# RP2350.net
KiCad netlist of a schematic drawn in Altium Designer
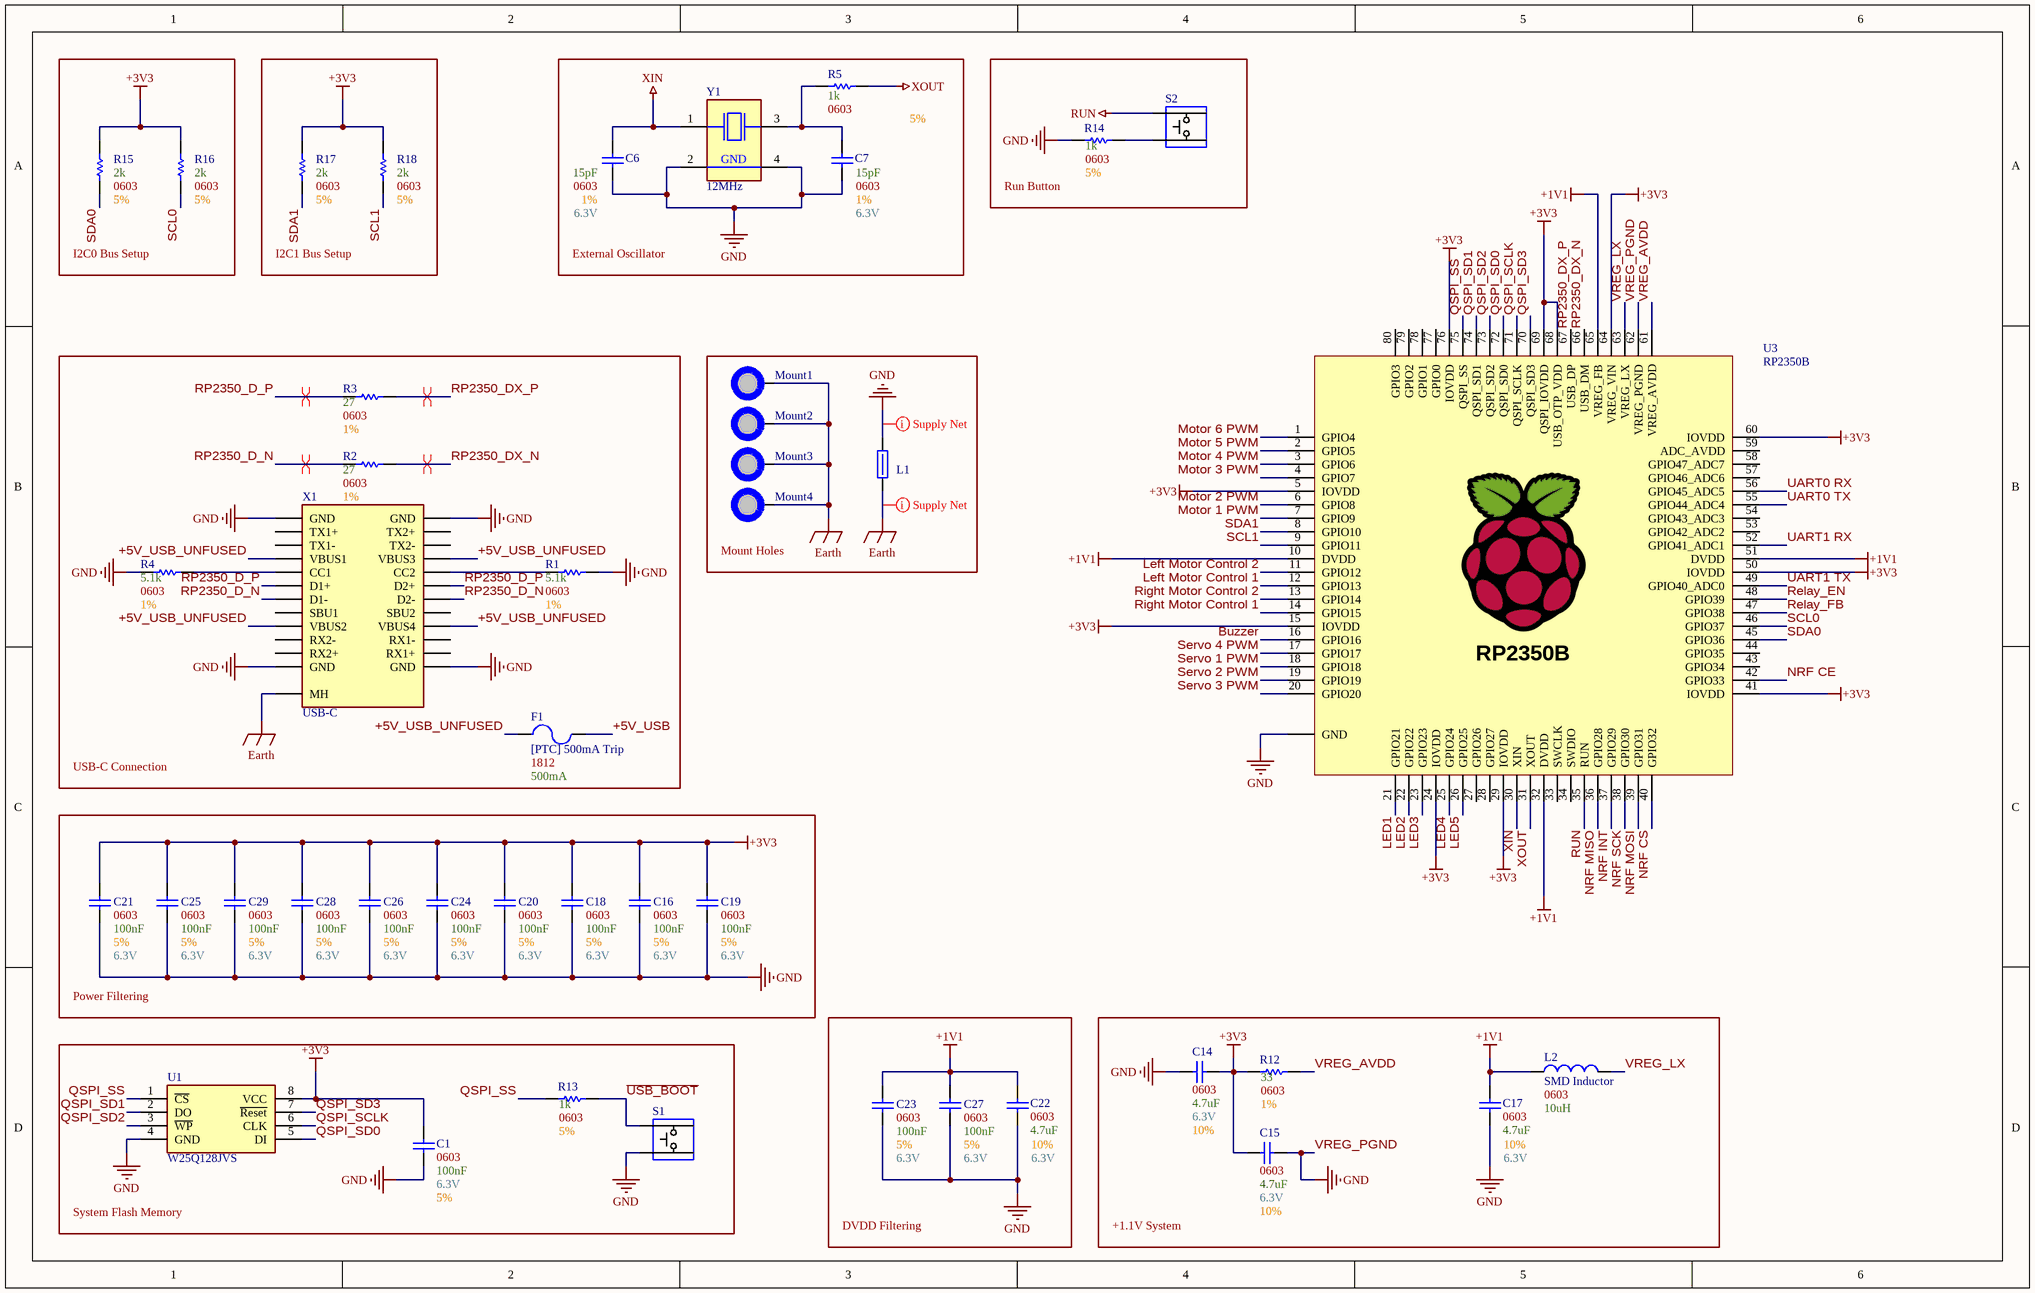
[diagram p0: RP2350.SchDoc]

(export (version "E")
  (design (tool "Eeschema 10.0.6"))
  (components
    (comp (ref "C1")
      (value "[Cap] SMD Nonpolarized")
      (footprint "[Cap] SMD 0603")
      (fields
        (field (name "SIZE PACKAGE") "0603")
        (field (name "CAPACITANCE") "100nF")
        (field (name "VOLTAGE") "6.3V")
        (field (name "TOLERANCE") "5%")
      )
      (libsource (lib "RADM Components") (part "[Cap] SMD Nonpolarized"))
    )
    (comp (ref "C6")
      (value "[Cap] SMD Nonpolarized")
      (footprint "[Cap] SMD 0603")
      (fields
        (field (name "SIZE PACKAGE") "0603")
        (field (name "CAPACITANCE") "15pF")
        (field (name "VOLTAGE") "6.3V")
        (field (name "TOLERANCE") "1%")
      )
      (libsource (lib "RADM Components") (part "[Cap] SMD Nonpolarized"))
    )
    (comp (ref "C7")
      (value "[Cap] SMD Nonpolarized")
      (footprint "[Cap] SMD 0603")
      (fields
        (field (name "SIZE PACKAGE") "0603")
        (field (name "CAPACITANCE") "15pF")
        (field (name "VOLTAGE") "6.3V")
        (field (name "TOLERANCE") "1%")
      )
      (libsource (lib "RADM Components") (part "[Cap] SMD Nonpolarized"))
    )
    (comp (ref "C14")
      (value "[Cap] SMD Nonpolarized")
      (footprint "[Cap] SMD 0603")
      (fields
        (field (name "SIZE PACKAGE") "0603")
        (field (name "CAPACITANCE") "4.7uF")
        (field (name "VOLTAGE") "6.3V")
        (field (name "TOLERANCE") "10%")
      )
      (libsource (lib "RADM Components") (part "[Cap] SMD Nonpolarized"))
    )
    (comp (ref "C15")
      (value "[Cap] SMD Nonpolarized")
      (footprint "[Cap] SMD 0603")
      (fields
        (field (name "SIZE PACKAGE") "0603")
        (field (name "CAPACITANCE") "4.7uF")
        (field (name "VOLTAGE") "6.3V")
        (field (name "TOLERANCE") "10%")
      )
      (libsource (lib "RADM Components") (part "[Cap] SMD Nonpolarized"))
    )
    (comp (ref "C16")
      (value "[Cap] SMD Nonpolarized")
      (footprint "[Cap] SMD 0603")
      (fields
        (field (name "SIZE PACKAGE") "0603")
        (field (name "CAPACITANCE") "100nF")
        (field (name "VOLTAGE") "6.3V")
        (field (name "TOLERANCE") "5%")
      )
      (libsource (lib "RADM Components") (part "[Cap] SMD Nonpolarized"))
    )
    (comp (ref "C17")
      (value "[Cap] SMD Nonpolarized")
      (footprint "[Cap] SMD 0603")
      (fields
        (field (name "SIZE PACKAGE") "0603")
        (field (name "CAPACITANCE") "4.7uF")
        (field (name "VOLTAGE") "6.3V")
        (field (name "TOLERANCE") "10%")
      )
      (libsource (lib "RADM Components") (part "[Cap] SMD Nonpolarized"))
    )
    (comp (ref "C18")
      (value "[Cap] SMD Nonpolarized")
      (footprint "[Cap] SMD 0603")
      (fields
        (field (name "SIZE PACKAGE") "0603")
        (field (name "CAPACITANCE") "100nF")
        (field (name "VOLTAGE") "6.3V")
        (field (name "TOLERANCE") "5%")
      )
      (libsource (lib "RADM Components") (part "[Cap] SMD Nonpolarized"))
    )
    (comp (ref "C19")
      (value "[Cap] SMD Nonpolarized")
      (footprint "[Cap] SMD 0603")
      (fields
        (field (name "SIZE PACKAGE") "0603")
        (field (name "CAPACITANCE") "100nF")
        (field (name "VOLTAGE") "6.3V")
        (field (name "TOLERANCE") "5%")
      )
      (libsource (lib "RADM Components") (part "[Cap] SMD Nonpolarized"))
    )
    (comp (ref "C20")
      (value "[Cap] SMD Nonpolarized")
      (footprint "[Cap] SMD 0603")
      (fields
        (field (name "SIZE PACKAGE") "0603")
        (field (name "CAPACITANCE") "100nF")
        (field (name "VOLTAGE") "6.3V")
        (field (name "TOLERANCE") "5%")
      )
      (libsource (lib "RADM Components") (part "[Cap] SMD Nonpolarized"))
    )
    (comp (ref "C21")
      (value "[Cap] SMD Nonpolarized")
      (footprint "[Cap] SMD 0603")
      (fields
        (field (name "SIZE PACKAGE") "0603")
        (field (name "CAPACITANCE") "100nF")
        (field (name "VOLTAGE") "6.3V")
        (field (name "TOLERANCE") "5%")
      )
      (libsource (lib "RADM Components") (part "[Cap] SMD Nonpolarized"))
    )
    (comp (ref "C22")
      (value "[Cap] SMD Nonpolarized")
      (footprint "[Cap] SMD 0603")
      (fields
        (field (name "SIZE PACKAGE") "0603")
        (field (name "CAPACITANCE") "4.7uF")
        (field (name "VOLTAGE") "6.3V")
        (field (name "TOLERANCE") "10%")
      )
      (libsource (lib "RADM Components") (part "[Cap] SMD Nonpolarized"))
    )
    (comp (ref "C23")
      (value "[Cap] SMD Nonpolarized")
      (footprint "[Cap] SMD 0603")
      (fields
        (field (name "SIZE PACKAGE") "0603")
        (field (name "CAPACITANCE") "100nF")
        (field (name "VOLTAGE") "6.3V")
        (field (name "TOLERANCE") "5%")
      )
      (libsource (lib "RADM Components") (part "[Cap] SMD Nonpolarized"))
    )
    (comp (ref "C24")
      (value "[Cap] SMD Nonpolarized")
      (footprint "[Cap] SMD 0603")
      (fields
        (field (name "SIZE PACKAGE") "0603")
        (field (name "CAPACITANCE") "100nF")
        (field (name "VOLTAGE") "6.3V")
        (field (name "TOLERANCE") "5%")
      )
      (libsource (lib "RADM Components") (part "[Cap] SMD Nonpolarized"))
    )
    (comp (ref "C25")
      (value "[Cap] SMD Nonpolarized")
      (footprint "[Cap] SMD 0603")
      (fields
        (field (name "SIZE PACKAGE") "0603")
        (field (name "CAPACITANCE") "100nF")
        (field (name "VOLTAGE") "6.3V")
        (field (name "TOLERANCE") "5%")
      )
      (libsource (lib "RADM Components") (part "[Cap] SMD Nonpolarized"))
    )
    (comp (ref "C26")
      (value "[Cap] SMD Nonpolarized")
      (footprint "[Cap] SMD 0603")
      (fields
        (field (name "SIZE PACKAGE") "0603")
        (field (name "CAPACITANCE") "100nF")
        (field (name "VOLTAGE") "6.3V")
        (field (name "TOLERANCE") "5%")
      )
      (libsource (lib "RADM Components") (part "[Cap] SMD Nonpolarized"))
    )
    (comp (ref "C27")
      (value "[Cap] SMD Nonpolarized")
      (footprint "[Cap] SMD 0603")
      (fields
        (field (name "SIZE PACKAGE") "0603")
        (field (name "CAPACITANCE") "100nF")
        (field (name "VOLTAGE") "6.3V")
        (field (name "TOLERANCE") "5%")
      )
      (libsource (lib "RADM Components") (part "[Cap] SMD Nonpolarized"))
    )
    (comp (ref "C28")
      (value "[Cap] SMD Nonpolarized")
      (footprint "[Cap] SMD 0603")
      (fields
        (field (name "SIZE PACKAGE") "0603")
        (field (name "CAPACITANCE") "100nF")
        (field (name "VOLTAGE") "6.3V")
        (field (name "TOLERANCE") "5%")
      )
      (libsource (lib "RADM Components") (part "[Cap] SMD Nonpolarized"))
    )
    (comp (ref "C29")
      (value "[Cap] SMD Nonpolarized")
      (footprint "[Cap] SMD 0603")
      (fields
        (field (name "SIZE PACKAGE") "0603")
        (field (name "CAPACITANCE") "100nF")
        (field (name "VOLTAGE") "6.3V")
        (field (name "TOLERANCE") "5%")
      )
      (libsource (lib "RADM Components") (part "[Cap] SMD Nonpolarized"))
    )
    (comp (ref "F1")
      (value "[PTC] 500mA Trip")
      (footprint "[PTC] 500mA Trip")
      (description "MF-MSMF050-2")
      (fields (field (name "SIZE PACKAGE") "1812") (field (name "TRIP CURRENT") "500mA"))
      (libsource (lib "RADM Components") (part "[PTC] 500mA Trip"))
    )
    (comp (ref "L1")
      (value "652-MH2029-300Y")
      (footprint "[Ferrite] SMD Bead 0805 (1)")
      (libsource (lib "RADM Components") (part "[Ferrite] SMD Ferrite Bead (1)"))
    )
    (comp (ref "L2")
      (value "SMD Inductor")
      (footprint "[Inductor] SMD 0603")
      (fields (field (name "SIZE PACKAGE") "0603") (field (name "INDUCTANCE") "10uH"))
      (libsource (lib "RADM Components") (part "[Inductor] SMD Inductor"))
    )
    (comp (ref "Mount1")
      (value "M3 Mount Hole")
      (footprint "[Mount] M3 Mount Hole")
      (description "Place at least 4.5mm from board edge. Plated.")
      (libsource (lib "RADM Connectors") (part "[Mount] M3 Mount Hole"))
    )
    (comp (ref "Mount2")
      (value "M3 Mount Hole")
      (footprint "[Mount] M3 Mount Hole")
      (description "Place at least 4.5mm from board edge. Plated.")
      (libsource (lib "RADM Connectors") (part "[Mount] M3 Mount Hole"))
    )
    (comp (ref "Mount3")
      (value "M3 Mount Hole")
      (footprint "[Mount] M3 Mount Hole")
      (description "Place at least 4.5mm from board edge. Plated.")
      (libsource (lib "RADM Connectors") (part "[Mount] M3 Mount Hole"))
    )
    (comp (ref "Mount4")
      (value "M3 Mount Hole")
      (footprint "[Mount] M3 Mount Hole")
      (description "Place at least 4.5mm from board edge. Plated.")
      (libsource (lib "RADM Connectors") (part "[Mount] M3 Mount Hole"))
    )
    (comp (ref "R1")
      (value "[Res] SMD Resistor")
      (footprint "[Res] SMD 0603")
      (description "Generic")
      (fields
        (field (name "TOLERANCE") "1%")
        (field (name "RESISTANCE") "5.1k")
        (field (name "SIZE PACKAGE") "0603")
      )
      (libsource (lib "RADM Components") (part "[Res] SMD Resistor"))
    )
    (comp (ref "R2")
      (value "[Res] SMD Resistor")
      (footprint "[Res] SMD 0603")
      (description "Generic")
      (fields
        (field (name "TOLERANCE") "1%")
        (field (name "RESISTANCE") "27")
        (field (name "SIZE PACKAGE") "0603")
      )
      (libsource (lib "RADM Components") (part "[Res] SMD Resistor"))
    )
    (comp (ref "R3")
      (value "[Res] SMD Resistor")
      (footprint "[Res] SMD 0603")
      (description "Generic")
      (fields
        (field (name "TOLERANCE") "1%")
        (field (name "RESISTANCE") "27")
        (field (name "SIZE PACKAGE") "0603")
      )
      (libsource (lib "RADM Components") (part "[Res] SMD Resistor"))
    )
    (comp (ref "R4")
      (value "[Res] SMD Resistor")
      (footprint "[Res] SMD 0603")
      (description "Generic")
      (fields
        (field (name "TOLERANCE") "1%")
        (field (name "RESISTANCE") "5.1k")
        (field (name "SIZE PACKAGE") "0603")
      )
      (libsource (lib "RADM Components") (part "[Res] SMD Resistor"))
    )
    (comp (ref "R5")
      (value "[Res] SMD Resistor")
      (footprint "[Res] SMD 0603")
      (description "Generic")
      (fields
        (field (name "RESISTANCE") "1k")
        (field (name "SIZE PACKAGE") "0603")
        (field (name "TOLERANCE") "5%")
      )
      (libsource (lib "RADM Components") (part "[Res] SMD Resistor"))
    )
    (comp (ref "R12")
      (value "[Res] SMD Resistor")
      (footprint "[Res] SMD 0603")
      (description "Generic")
      (fields
        (field (name "RESISTANCE") "33")
        (field (name "SIZE PACKAGE") "0603")
        (field (name "TOLERANCE") "1%")
      )
      (libsource (lib "RADM Components") (part "[Res] SMD Resistor"))
    )
    (comp (ref "R13")
      (value "[Res] SMD Resistor")
      (footprint "[Res] SMD 0603")
      (description "Generic")
      (fields
        (field (name "RESISTANCE") "1k")
        (field (name "SIZE PACKAGE") "0603")
        (field (name "TOLERANCE") "5%")
      )
      (libsource (lib "RADM Components") (part "[Res] SMD Resistor"))
    )
    (comp (ref "R14")
      (value "[Res] SMD Resistor")
      (footprint "[Res] SMD 0603")
      (description "Generic")
      (fields
        (field (name "RESISTANCE") "1k")
        (field (name "SIZE PACKAGE") "0603")
        (field (name "TOLERANCE") "5%")
      )
      (libsource (lib "RADM Components") (part "[Res] SMD Resistor"))
    )
    (comp (ref "R15")
      (value "[Res] SMD Resistor")
      (footprint "[Res] SMD 0603")
      (description "Generic")
      (fields
        (field (name "RESISTANCE") "2k")
        (field (name "SIZE PACKAGE") "0603")
        (field (name "TOLERANCE") "5%")
      )
      (libsource (lib "RADM Components") (part "[Res] SMD Resistor"))
    )
    (comp (ref "R16")
      (value "[Res] SMD Resistor")
      (footprint "[Res] SMD 0603")
      (description "Generic")
      (fields
        (field (name "RESISTANCE") "2k")
        (field (name "SIZE PACKAGE") "0603")
        (field (name "TOLERANCE") "5%")
      )
      (libsource (lib "RADM Components") (part "[Res] SMD Resistor"))
    )
    (comp (ref "R17")
      (value "[Res] SMD Resistor")
      (footprint "[Res] SMD 0603")
      (description "Generic")
      (fields
        (field (name "RESISTANCE") "2k")
        (field (name "SIZE PACKAGE") "0603")
        (field (name "TOLERANCE") "5%")
      )
      (libsource (lib "RADM Components") (part "[Res] SMD Resistor"))
    )
    (comp (ref "R18")
      (value "[Res] SMD Resistor")
      (footprint "[Res] SMD 0603")
      (description "Generic")
      (fields
        (field (name "RESISTANCE") "2k")
        (field (name "SIZE PACKAGE") "0603")
        (field (name "TOLERANCE") "5%")
      )
      (libsource (lib "RADM Components") (part "[Res] SMD Resistor"))
    )
    (comp (ref "S1")
      (value "Standard pushbutton")
      (footprint "[Switch] Pushbutton")
      (libsource (lib "RADM Components") (part "[Switch] Pushbutton"))
    )
    (comp (ref "S2")
      (value "Standard pushbutton")
      (footprint "[Switch] Pushbutton")
      (libsource (lib "RADM Components") (part "[Switch] Pushbutton"))
    )
    (comp (ref "U1")
      (value "W25Q128JVS")
      (footprint "[Mem] 16Mb Flash Memory")
      (description "W25Q128JVSIQ TR")
      (libsource (lib "RADM Components") (part "[Mem] 16Mb Flash Memory"))
    )
    (comp (ref "U3")
      (value "RP2350B")
      (footprint "[MCU] RP2350B")
      (description "QFN-80 Package")
      (libsource (lib "RADM Components") (part "[MCU] RP2350B"))
    )
    (comp (ref "X1")
      (value "USB-C")
      (footprint "[Port] USB-C")
      (libsource (lib "RADM Connectors") (part "[Port] USB Type-C"))
    )
    (comp (ref "Y1")
      (value "12MHz")
      (footprint "[XTAL] SMD 12MHz")
      (description "815-ABM8-272-T3")
      (libsource (lib "RADM Components") (part "[XTAL] SMD 12MHz"))
    )
  )
  (nets
    (net (code "1") (name "+1V1") (class "Default")
      (node (ref "C17") (pin "2") (pinfunction "2_2") (pintype "passive"))
      (node (ref "C22") (pin "2") (pinfunction "2_2") (pintype "passive"))
      (node (ref "C23") (pin "2") (pinfunction "2_2") (pintype "passive"))
      (node (ref "C27") (pin "2") (pinfunction "2_2") (pintype "passive"))
      (node (ref "L2") (pin "1") (pinfunction "1_1") (pintype "passive"))
      (node (ref "U3") (pin "10") (pinfunction "DVDD_10") (pintype "passive"))
      (node (ref "U3") (pin "32") (pinfunction "DVDD_32") (pintype "passive"))
      (node (ref "U3") (pin "51") (pinfunction "DVDD_51") (pintype "passive"))
      (node (ref "U3") (pin "65") (pinfunction "VREG_FB_65") (pintype "passive"))
    )
    (net (code "2") (name "+3V3") (class "Default")
      (node (ref "C1") (pin "1") (pinfunction "1_1") (pintype "passive"))
      (node (ref "C14") (pin "1") (pinfunction "1_1") (pintype "passive"))
      (node (ref "C15") (pin "2") (pinfunction "2_2") (pintype "passive"))
      (node (ref "C16") (pin "2") (pinfunction "2_2") (pintype "passive"))
      (node (ref "C18") (pin "2") (pinfunction "2_2") (pintype "passive"))
      (node (ref "C19") (pin "2") (pinfunction "2_2") (pintype "passive"))
      (node (ref "C20") (pin "2") (pinfunction "2_2") (pintype "passive"))
      (node (ref "C21") (pin "2") (pinfunction "2_2") (pintype "passive"))
      (node (ref "C24") (pin "2") (pinfunction "2_2") (pintype "passive"))
      (node (ref "C25") (pin "2") (pinfunction "2_2") (pintype "passive"))
      (node (ref "C26") (pin "2") (pinfunction "2_2") (pintype "passive"))
      (node (ref "C28") (pin "2") (pinfunction "2_2") (pintype "passive"))
      (node (ref "C29") (pin "2") (pinfunction "2_2") (pintype "passive"))
      (node (ref "R12") (pin "2") (pinfunction "2_2") (pintype "passive"))
      (node (ref "R15") (pin "2") (pinfunction "2_2") (pintype "passive"))
      (node (ref "R16") (pin "2") (pinfunction "2_2") (pintype "passive"))
      (node (ref "R17") (pin "2") (pinfunction "2_2") (pintype "passive"))
      (node (ref "R18") (pin "2") (pinfunction "2_2") (pintype "passive"))
      (node (ref "U1") (pin "8") (pinfunction "VCC_8") (pintype "passive"))
      (node (ref "U3") (pin "15") (pinfunction "IOVDD_15") (pintype "passive"))
      (node (ref "U3") (pin "24") (pinfunction "IOVDD_24") (pintype "passive"))
      (node (ref "U3") (pin "29") (pinfunction "IOVDD_29") (pintype "passive"))
      (node (ref "U3") (pin "41") (pinfunction "IOVDD_41") (pintype "passive"))
      (node (ref "U3") (pin "5") (pinfunction "IOVDD_5") (pintype "passive"))
      (node (ref "U3") (pin "50") (pinfunction "IOVDD_50") (pintype "passive"))
      (node (ref "U3") (pin "60") (pinfunction "IOVDD_60") (pintype "passive"))
      (node (ref "U3") (pin "64") (pinfunction "VREG_VIN_64") (pintype "passive"))
      (node (ref "U3") (pin "68") (pinfunction "USB_OTP_VDD_68") (pintype "passive"))
      (node (ref "U3") (pin "69") (pinfunction "QSPI_IOVDD_69") (pintype "passive"))
      (node (ref "U3") (pin "76") (pinfunction "IOVDD_76") (pintype "passive"))
    )
    (net (code "3") (name "/+5V_USB") (class "Default")
      (node (ref "F1") (pin "2") (pinfunction "2_2") (pintype "passive"))
    )
    (net (code "4") (name "/+5V_USB_UNFUSED") (class "Default")
      (node (ref "F1") (pin "1") (pinfunction "1_1") (pintype "passive"))
      (node (ref "X1") (pin "A4") (pinfunction "VBUS1_A4") (pintype "passive"))
      (node (ref "X1") (pin "A9") (pinfunction "VBUS2_A9") (pintype "passive"))
      (node (ref "X1") (pin "B4") (pinfunction "VBUS3_B4") (pintype "passive"))
      (node (ref "X1") (pin "B9") (pinfunction "VBUS4_B9") (pintype "passive"))
    )
    (net (code "5") (name "/Buzzer") (class "Default")
      (node (ref "U3") (pin "16") (pinfunction "GPIO16_16") (pintype "passive"))
    )
    (net (code "6") (name "/LED1") (class "Default")
      (node (ref "U3") (pin "21") (pinfunction "GPIO21_21") (pintype "passive"))
    )
    (net (code "7") (name "/LED2") (class "Default")
      (node (ref "U3") (pin "22") (pinfunction "GPIO22_22") (pintype "passive"))
    )
    (net (code "8") (name "/LED3") (class "Default")
      (node (ref "U3") (pin "23") (pinfunction "GPIO23_23") (pintype "passive"))
    )
    (net (code "9") (name "/LED4") (class "Default")
      (node (ref "U3") (pin "25") (pinfunction "GPIO24_25") (pintype "passive"))
    )
    (net (code "10") (name "/LED5") (class "Default")
      (node (ref "U3") (pin "26") (pinfunction "GPIO25_26") (pintype "passive"))
    )
    (net (code "11") (name "/Left Motor Control 1") (class "Default")
      (node (ref "U3") (pin "12") (pinfunction "GPIO13_12") (pintype "passive"))
    )
    (net (code "12") (name "/Left Motor Control 2") (class "Default")
      (node (ref "U3") (pin "11") (pinfunction "GPIO12_11") (pintype "passive"))
    )
    (net (code "13") (name "/Motor 1 PWM") (class "Default")
      (node (ref "U3") (pin "7") (pinfunction "GPIO9_7") (pintype "passive"))
    )
    (net (code "14") (name "/Motor 2 PWM") (class "Default")
      (node (ref "U3") (pin "6") (pinfunction "GPIO8_6") (pintype "passive"))
    )
    (net (code "15") (name "/Motor 3 PWM") (class "Default")
      (node (ref "U3") (pin "4") (pinfunction "GPIO7_4") (pintype "passive"))
    )
    (net (code "16") (name "/Motor 4 PWM") (class "Default")
      (node (ref "U3") (pin "3") (pinfunction "GPIO6_3") (pintype "passive"))
    )
    (net (code "17") (name "/Motor 5 PWM") (class "Default")
      (node (ref "U3") (pin "2") (pinfunction "GPIO5_2") (pintype "passive"))
    )
    (net (code "18") (name "/Motor 6 PWM") (class "Default")
      (node (ref "U3") (pin "1") (pinfunction "GPIO4_1") (pintype "passive"))
    )
    (net (code "19") (name "/NRF CE") (class "Default")
      (node (ref "U3") (pin "42") (pinfunction "GPIO33_42") (pintype "passive"))
    )
    (net (code "20") (name "/NRF CS") (class "Default")
      (node (ref "U3") (pin "40") (pinfunction "GPIO32_40") (pintype "passive"))
    )
    (net (code "21") (name "/NRF INT") (class "Default")
      (node (ref "U3") (pin "37") (pinfunction "GPIO29_37") (pintype "passive"))
    )
    (net (code "22") (name "/NRF MISO") (class "Default")
      (node (ref "U3") (pin "36") (pinfunction "GPIO28_36") (pintype "passive"))
    )
    (net (code "23") (name "/NRF MOSI") (class "Default")
      (node (ref "U3") (pin "39") (pinfunction "GPIO31_39") (pintype "passive"))
    )
    (net (code "24") (name "/NRF SCK") (class "Default")
      (node (ref "U3") (pin "38") (pinfunction "GPIO30_38") (pintype "passive"))
    )
    (net (code "25") (name "/QSPI_SCLK") (class "Default")
      (node (ref "U1") (pin "6") (pinfunction "CLK_6") (pintype "passive"))
      (node (ref "U3") (pin "71") (pinfunction "QSPI_SCLK_71") (pintype "passive"))
    )
    (net (code "26") (name "/QSPI_SD0") (class "Default")
      (node (ref "U1") (pin "5") (pinfunction "DI_5") (pintype "passive"))
      (node (ref "U3") (pin "72") (pinfunction "QSPI_SD0_72") (pintype "passive"))
    )
    (net (code "27") (name "/QSPI_SD1") (class "Default")
      (node (ref "U1") (pin "2") (pinfunction "DO_2") (pintype "passive"))
      (node (ref "U3") (pin "74") (pinfunction "QSPI_SD1_74") (pintype "passive"))
    )
    (net (code "28") (name "/QSPI_SD2") (class "Default")
      (node (ref "U1") (pin "3") (pinfunction "~{WP}_3") (pintype "passive"))
      (node (ref "U3") (pin "73") (pinfunction "QSPI_SD2_73") (pintype "passive"))
    )
    (net (code "29") (name "/QSPI_SD3") (class "Default")
      (node (ref "U1") (pin "7") (pinfunction "~{Reset}_7") (pintype "passive"))
      (node (ref "U3") (pin "70") (pinfunction "QSPI_SD3_70") (pintype "passive"))
    )
    (net (code "30") (name "/QSPI_SS") (class "Default")
      (node (ref "R13") (pin "2") (pinfunction "2_2") (pintype "passive"))
      (node (ref "U1") (pin "1") (pinfunction "~{CS}_1") (pintype "passive"))
      (node (ref "U3") (pin "75") (pinfunction "QSPI_SS_75") (pintype "passive"))
    )
    (net (code "31") (name "/RP2350_DX_N") (class "Default")
      (node (ref "R2") (pin "2") (pinfunction "2_2") (pintype "passive"))
      (node (ref "U3") (pin "66") (pinfunction "USB_DM_66") (pintype "passive"))
    )
    (net (code "32") (name "/RP2350_DX_P") (class "Default")
      (node (ref "R3") (pin "2") (pinfunction "2_2") (pintype "passive"))
      (node (ref "U3") (pin "67") (pinfunction "USB_DP_67") (pintype "passive"))
    )
    (net (code "33") (name "/RP2350_D_N") (class "Default")
      (node (ref "R2") (pin "1") (pinfunction "1_1") (pintype "passive"))
      (node (ref "X1") (pin "A7") (pinfunction "D1-_A7") (pintype "passive"))
      (node (ref "X1") (pin "B7") (pinfunction "D2-_B7") (pintype "passive"))
    )
    (net (code "34") (name "/RP2350_D_P") (class "Default")
      (node (ref "R3") (pin "1") (pinfunction "1_1") (pintype "passive"))
      (node (ref "X1") (pin "A6") (pinfunction "D1+_A6") (pintype "passive"))
      (node (ref "X1") (pin "B6") (pinfunction "D2+_B6") (pintype "passive"))
    )
    (net (code "35") (name "/Relay_EN") (class "Default")
      (node (ref "U3") (pin "48") (pinfunction "GPIO39_48") (pintype "passive"))
    )
    (net (code "36") (name "/Relay_FB") (class "Default")
      (node (ref "U3") (pin "47") (pinfunction "GPIO38_47") (pintype "passive"))
    )
    (net (code "37") (name "/Right Motor Control 1") (class "Default")
      (node (ref "U3") (pin "14") (pinfunction "GPIO15_14") (pintype "passive"))
    )
    (net (code "38") (name "/Right Motor Control 2") (class "Default")
      (node (ref "U3") (pin "13") (pinfunction "GPIO14_13") (pintype "passive"))
    )
    (net (code "39") (name "/SCL0") (class "Default")
      (node (ref "R16") (pin "1") (pinfunction "1_1") (pintype "passive"))
      (node (ref "U3") (pin "46") (pinfunction "GPIO37_46") (pintype "passive"))
    )
    (net (code "40") (name "/SCL1") (class "Default")
      (node (ref "R18") (pin "1") (pinfunction "1_1") (pintype "passive"))
      (node (ref "U3") (pin "9") (pinfunction "GPIO11_9") (pintype "passive"))
    )
    (net (code "41") (name "/SDA0") (class "Default")
      (node (ref "R15") (pin "1") (pinfunction "1_1") (pintype "passive"))
      (node (ref "U3") (pin "45") (pinfunction "GPIO36_45") (pintype "passive"))
    )
    (net (code "42") (name "/SDA1") (class "Default")
      (node (ref "R17") (pin "1") (pinfunction "1_1") (pintype "passive"))
      (node (ref "U3") (pin "8") (pinfunction "GPIO10_8") (pintype "passive"))
    )
    (net (code "43") (name "/Servo 1 PWM") (class "Default")
      (node (ref "U3") (pin "18") (pinfunction "GPIO18_18") (pintype "passive"))
    )
    (net (code "44") (name "/Servo 2 PWM") (class "Default")
      (node (ref "U3") (pin "19") (pinfunction "GPIO19_19") (pintype "passive"))
    )
    (net (code "45") (name "/Servo 3 PWM") (class "Default")
      (node (ref "U3") (pin "20") (pinfunction "GPIO20_20") (pintype "passive"))
    )
    (net (code "46") (name "/Servo 4 PWM") (class "Default")
      (node (ref "U3") (pin "17") (pinfunction "GPIO17_17") (pintype "passive"))
    )
    (net (code "47") (name "/UART0 RX") (class "Default")
      (node (ref "U3") (pin "56") (pinfunction "GPIO45_ADC5_56") (pintype "passive"))
    )
    (net (code "48") (name "/UART0 TX") (class "Default")
      (node (ref "U3") (pin "55") (pinfunction "GPIO44_ADC4_55") (pintype "passive"))
    )
    (net (code "49") (name "/UART1 RX") (class "Default")
      (node (ref "U3") (pin "52") (pinfunction "GPIO41_ADC1_52") (pintype "passive"))
    )
    (net (code "50") (name "/UART1 TX") (class "Default")
      (node (ref "U3") (pin "49") (pinfunction "GPIO40_ADC0_49") (pintype "passive"))
    )
    (net (code "51") (name "/VREG_AVDD") (class "Default")
      (node (ref "R12") (pin "1") (pinfunction "1_1") (pintype "passive"))
      (node (ref "U3") (pin "61") (pinfunction "VREG_AVDD_61") (pintype "passive"))
    )
    (net (code "52") (name "/VREG_LX") (class "Default")
      (node (ref "L2") (pin "2") (pinfunction "2_2") (pintype "passive"))
      (node (ref "U3") (pin "63") (pinfunction "VREG_LX_63") (pintype "passive"))
    )
    (net (code "53") (name "/~{USB_BOOT}") (class "Default")
      (node (ref "R13") (pin "1") (pinfunction "1_1") (pintype "passive"))
      (node (ref "S1") (pin "1") (pintype "power_in"))
    )
    (net (code "54") (name "Earth") (class "Default")
      (node (ref "L1") (pin "1") (pinfunction "1_1") (pintype "passive"))
      (node (ref "Mount1") (pin "1") (pintype "power_in"))
      (node (ref "Mount2") (pin "1") (pintype "power_in"))
      (node (ref "Mount3") (pin "1") (pintype "power_in"))
      (node (ref "Mount4") (pin "1") (pintype "power_in"))
      (node (ref "X1") (pin "MH") (pinfunction "MH_MH") (pintype "passive"))
    )
    (net (code "55") (name "GND") (class "Default")
      (node (ref "C1") (pin "2") (pinfunction "2_2") (pintype "passive"))
      (node (ref "C14") (pin "2") (pinfunction "2_2") (pintype "passive"))
      (node (ref "C15") (pin "1") (pinfunction "1_1") (pintype "passive"))
      (node (ref "C16") (pin "1") (pinfunction "1_1") (pintype "passive"))
      (node (ref "C17") (pin "1") (pinfunction "1_1") (pintype "passive"))
      (node (ref "C18") (pin "1") (pinfunction "1_1") (pintype "passive"))
      (node (ref "C19") (pin "1") (pinfunction "1_1") (pintype "passive"))
      (node (ref "C20") (pin "1") (pinfunction "1_1") (pintype "passive"))
      (node (ref "C21") (pin "1") (pinfunction "1_1") (pintype "passive"))
      (node (ref "C22") (pin "1") (pinfunction "1_1") (pintype "passive"))
      (node (ref "C23") (pin "1") (pinfunction "1_1") (pintype "passive"))
      (node (ref "C24") (pin "1") (pinfunction "1_1") (pintype "passive"))
      (node (ref "C25") (pin "1") (pinfunction "1_1") (pintype "passive"))
      (node (ref "C26") (pin "1") (pinfunction "1_1") (pintype "passive"))
      (node (ref "C27") (pin "1") (pinfunction "1_1") (pintype "passive"))
      (node (ref "C28") (pin "1") (pinfunction "1_1") (pintype "passive"))
      (node (ref "C29") (pin "1") (pinfunction "1_1") (pintype "passive"))
      (node (ref "C6") (pin "1") (pinfunction "1_1") (pintype "passive"))
      (node (ref "C7") (pin "1") (pinfunction "1_1") (pintype "passive"))
      (node (ref "L1") (pin "2") (pinfunction "2_2") (pintype "passive"))
      (node (ref "R1") (pin "2") (pinfunction "2_2") (pintype "passive"))
      (node (ref "R14") (pin "2") (pinfunction "2_2") (pintype "passive"))
      (node (ref "R4") (pin "1") (pinfunction "1_1") (pintype "passive"))
      (node (ref "S1") (pin "2") (pintype "power_in"))
      (node (ref "U1") (pin "4") (pinfunction "GND_4") (pintype "passive"))
      (node (ref "U3") (pin "62") (pinfunction "VREG_PGND_62") (pintype "passive"))
      (node (ref "U3") (pin "Pad") (pinfunction "GND_Pad") (pintype "passive"))
      (node (ref "X1") (pin "A1") (pinfunction "GND_A1") (pintype "passive"))
      (node (ref "X1") (pin "A12") (pinfunction "GND_A12") (pintype "passive"))
      (node (ref "X1") (pin "B1") (pinfunction "GND_B1") (pintype "passive"))
      (node (ref "X1") (pin "B12") (pinfunction "GND_B12") (pintype "passive"))
      (node (ref "Y1") (pin "2") (pinfunction "GND_2") (pintype "power_in"))
      (node (ref "Y1") (pin "4") (pinfunction "GND_4") (pintype "power_in"))
    )
    (net (code "56") (name "Net-(R14-Pad1)") (class "Default")
      (node (ref "R14") (pin "1") (pinfunction "1_1") (pintype "passive"))
      (node (ref "S2") (pin "2") (pintype "power_in"))
    )
    (net (code "57") (name "Net-(X1-CC1)") (class "Default")
      (node (ref "R4") (pin "2") (pinfunction "2_2") (pintype "passive"))
      (node (ref "X1") (pin "A5") (pinfunction "CC1_A5") (pintype "passive"))
    )
    (net (code "58") (name "Net-(X1-CC2)") (class "Default")
      (node (ref "R1") (pin "1") (pinfunction "1_1") (pintype "passive"))
      (node (ref "X1") (pin "B5") (pinfunction "CC2_B5") (pintype "passive"))
    )
    (net (code "59") (name "Net-(Y1-XTAL2)") (class "Default")
      (node (ref "C7") (pin "2") (pinfunction "2_2") (pintype "passive"))
      (node (ref "R5") (pin "2") (pinfunction "2_2") (pintype "passive"))
      (node (ref "Y1") (pin "3") (pinfunction "XTAL2_3") (pintype "power_in"))
    )
    (net (code "60") (name "RUN") (class "Default")
      (node (ref "S2") (pin "1") (pintype "power_in"))
      (node (ref "U3") (pin "35") (pinfunction "RUN_35") (pintype "passive"))
    )
    (net (code "61") (name "XIN") (class "Default")
      (node (ref "C6") (pin "2") (pinfunction "2_2") (pintype "passive"))
      (node (ref "U3") (pin "30") (pinfunction "XIN_30") (pintype "passive"))
      (node (ref "Y1") (pin "1") (pinfunction "XTAL1_1") (pintype "power_in"))
    )
    (net (code "62") (name "XOUT") (class "Default")
      (node (ref "R5") (pin "1") (pinfunction "1_1") (pintype "passive"))
      (node (ref "U3") (pin "31") (pinfunction "XOUT_31") (pintype "passive"))
    )
    (net (code "63") (name "unconnected-(U3-ADC_AVDD-Pad59)") (class "Default")
      (node (ref "U3") (pin "59") (pinfunction "ADC_AVDD_59") (pintype "passive"))
    )
    (net (code "64") (name "unconnected-(U3-GPIO0-Pad77)") (class "Default")
      (node (ref "U3") (pin "77") (pinfunction "GPIO0_77") (pintype "passive"))
    )
    (net (code "65") (name "unconnected-(U3-GPIO1-Pad78)") (class "Default")
      (node (ref "U3") (pin "78") (pinfunction "GPIO1_78") (pintype "passive"))
    )
    (net (code "66") (name "unconnected-(U3-GPIO2-Pad79)") (class "Default")
      (node (ref "U3") (pin "79") (pinfunction "GPIO2_79") (pintype "passive"))
    )
    (net (code "67") (name "unconnected-(U3-GPIO3-Pad80)") (class "Default")
      (node (ref "U3") (pin "80") (pinfunction "GPIO3_80") (pintype "passive"))
    )
    (net (code "68") (name "unconnected-(U3-GPIO26-Pad27)") (class "Default")
      (node (ref "U3") (pin "27") (pinfunction "GPIO26_27") (pintype "passive"))
    )
    (net (code "69") (name "unconnected-(U3-GPIO27-Pad28)") (class "Default")
      (node (ref "U3") (pin "28") (pinfunction "GPIO27_28") (pintype "passive"))
    )
    (net (code "70") (name "unconnected-(U3-GPIO34-Pad43)") (class "Default")
      (node (ref "U3") (pin "43") (pinfunction "GPIO34_43") (pintype "passive"))
    )
    (net (code "71") (name "unconnected-(U3-GPIO35-Pad44)") (class "Default")
      (node (ref "U3") (pin "44") (pinfunction "GPIO35_44") (pintype "passive"))
    )
    (net (code "72") (name "unconnected-(U3-GPIO42_ADC2-Pad53)") (class "Default")
      (node (ref "U3") (pin "53") (pinfunction "GPIO42_ADC2_53") (pintype "passive"))
    )
    (net (code "73") (name "unconnected-(U3-GPIO43_ADC3-Pad54)") (class "Default")
      (node (ref "U3") (pin "54") (pinfunction "GPIO43_ADC3_54") (pintype "passive"))
    )
    (net (code "74") (name "unconnected-(U3-GPIO46_ADC6-Pad57)") (class "Default")
      (node (ref "U3") (pin "57") (pinfunction "GPIO46_ADC6_57") (pintype "passive"))
    )
    (net (code "75") (name "unconnected-(U3-GPIO47_ADC7-Pad58)") (class "Default")
      (node (ref "U3") (pin "58") (pinfunction "GPIO47_ADC7_58") (pintype "passive"))
    )
    (net (code "76") (name "unconnected-(U3-SWCLK-Pad33)") (class "Default")
      (node (ref "U3") (pin "33") (pinfunction "SWCLK_33") (pintype "passive"))
    )
    (net (code "77") (name "unconnected-(U3-SWDIO-Pad34)") (class "Default")
      (node (ref "U3") (pin "34") (pinfunction "SWDIO_34") (pintype "passive"))
    )
    (net (code "78") (name "unconnected-(X1-RX1+-PadB11)") (class "Default")
      (node (ref "X1") (pin "B11") (pinfunction "RX1+_B11") (pintype "passive"))
    )
    (net (code "79") (name "unconnected-(X1-RX1--PadB10)") (class "Default")
      (node (ref "X1") (pin "B10") (pinfunction "RX1-_B10") (pintype "passive"))
    )
    (net (code "80") (name "unconnected-(X1-RX2+-PadA11)") (class "Default")
      (node (ref "X1") (pin "A11") (pinfunction "RX2+_A11") (pintype "passive"))
    )
    (net (code "81") (name "unconnected-(X1-RX2--PadA10)") (class "Default")
      (node (ref "X1") (pin "A10") (pinfunction "RX2-_A10") (pintype "passive"))
    )
    (net (code "82") (name "unconnected-(X1-SBU1-PadA8)") (class "Default")
      (node (ref "X1") (pin "A8") (pinfunction "SBU1_A8") (pintype "passive"))
    )
    (net (code "83") (name "unconnected-(X1-SBU2-PadB8)") (class "Default")
      (node (ref "X1") (pin "B8") (pinfunction "SBU2_B8") (pintype "passive"))
    )
    (net (code "84") (name "unconnected-(X1-TX1+-PadA2)") (class "Default")
      (node (ref "X1") (pin "A2") (pinfunction "TX1+_A2") (pintype "passive"))
    )
    (net (code "85") (name "unconnected-(X1-TX1--PadA3)") (class "Default")
      (node (ref "X1") (pin "A3") (pinfunction "TX1-_A3") (pintype "passive"))
    )
    (net (code "86") (name "unconnected-(X1-TX2+-PadB2)") (class "Default")
      (node (ref "X1") (pin "B2") (pinfunction "TX2+_B2") (pintype "passive"))
    )
    (net (code "87") (name "unconnected-(X1-TX2--PadB3)") (class "Default")
      (node (ref "X1") (pin "B3") (pinfunction "TX2-_B3") (pintype "passive"))
    )
  )
)
